# lamp-a-1.net
KiCad netlist of a schematic drawn in EAGLE
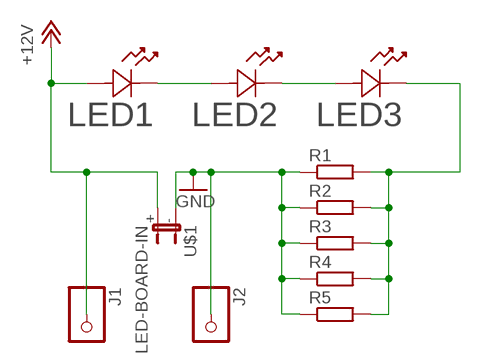
[diagram p0: schematic, sheet 1]

(export (version "E")
  (design (tool "Eeschema 10.0.6"))
  (components
    (comp (ref "J1")
      (value "LARGE-SOLDERPAD")
      (footprint "eagle-import:LARGE-SOLDERPAD")
      (libsource (lib "eagle-import") (part "LARGE-SOLDERPAD"))
    )
    (comp (ref "J2")
      (value "LARGE-SOLDERPAD")
      (footprint "eagle-import:LARGE-SOLDERPAD")
      (libsource (lib "eagle-import") (part "LARGE-SOLDERPAD"))
    )
    (comp (ref "LED1")
      (value "LED-2835LED_J2835_CRW-M")
      (footprint "eagle-import:LED_J2835_CRW-M")
      (fields
        (field (name "MANUFACTURER_PART_NUMBER") "JB2835AWT-W-U30GA0000-N0000001")
        (field (name "COPYRIGHT") "Copyright (C) 2024 Ultra Librarian. All rights reserved.")
      )
      (libsource (lib "eagle-import") (part "LED-2835LED_J2835_CRW-M"))
    )
    (comp (ref "LED2")
      (value "LED-2835LED_J2835_CRW-M")
      (footprint "eagle-import:LED_J2835_CRW-M")
      (fields
        (field (name "MANUFACTURER_PART_NUMBER") "JB2835AWT-W-U30GA0000-N0000001")
        (field (name "COPYRIGHT") "Copyright (C) 2024 Ultra Librarian. All rights reserved.")
      )
      (libsource (lib "eagle-import") (part "LED-2835LED_J2835_CRW-M"))
    )
    (comp (ref "LED3")
      (value "LED-2835LED_J2835_CRW-M")
      (footprint "eagle-import:LED_J2835_CRW-M")
      (fields
        (field (name "MANUFACTURER_PART_NUMBER") "JB2835AWT-W-U30GA0000-N0000001")
        (field (name "COPYRIGHT") "Copyright (C) 2024 Ultra Librarian. All rights reserved.")
      )
      (libsource (lib "eagle-import") (part "LED-2835LED_J2835_CRW-M"))
    )
    (comp (ref "R1")
      (value "R-EU_R0805")
      (footprint "eagle-import:R0805")
      (libsource (lib "eagle-import") (part "R-EU_R0805"))
    )
    (comp (ref "R2")
      (value "R-EU_R0805")
      (footprint "eagle-import:R0805")
      (libsource (lib "eagle-import") (part "R-EU_R0805"))
    )
    (comp (ref "R3")
      (value "R-EU_R0805")
      (footprint "eagle-import:R0805")
      (libsource (lib "eagle-import") (part "R-EU_R0805"))
    )
    (comp (ref "R4")
      (value "R-EU_R0805")
      (footprint "eagle-import:R0805")
      (libsource (lib "eagle-import") (part "R-EU_R0805"))
    )
    (comp (ref "R5")
      (value "R-EU_R0805")
      (footprint "eagle-import:R0805")
      (libsource (lib "eagle-import") (part "R-EU_R0805"))
    )
    (comp (ref "U$1")
      (value "LED-BOARD-IN")
      (footprint "eagle-import:LED-BOARD-IN")
      (libsource (lib "eagle-import") (part "LED-BOARD-IN"))
    )
  )
  (nets
    (net (code "1") (name "+12V") (class "Default")
      (node (ref "J1") (pin "P$1") (pinfunction "1_P$1") (pintype "passive"))
      (node (ref "LED1") (pin "2") (pinfunction "2_2") (pintype "passive"))
      (node (ref "U$1") (pin "+") (pinfunction "2_+") (pintype "passive"))
    )
    (net (code "2") (name "GND") (class "Default")
      (node (ref "J2") (pin "P$1") (pinfunction "1_P$1") (pintype "passive"))
      (node (ref "R1") (pin "1") (pinfunction "1_1") (pintype "passive"))
      (node (ref "R2") (pin "1") (pinfunction "1_1") (pintype "passive"))
      (node (ref "R3") (pin "1") (pinfunction "1_1") (pintype "passive"))
      (node (ref "R4") (pin "1") (pinfunction "1_1") (pintype "passive"))
      (node (ref "R5") (pin "1") (pinfunction "1_1") (pintype "passive"))
      (node (ref "U$1") (pin "-") (pinfunction "1_-") (pintype "passive"))
    )
    (net (code "3") (name "Net-(LED1-Pad1)") (class "Default")
      (node (ref "LED1") (pin "1") (pinfunction "1_1") (pintype "passive"))
      (node (ref "LED2") (pin "2") (pinfunction "2_2") (pintype "passive"))
    )
    (net (code "4") (name "Net-(LED2-Pad1)") (class "Default")
      (node (ref "LED2") (pin "1") (pinfunction "1_1") (pintype "passive"))
      (node (ref "LED3") (pin "2") (pinfunction "2_2") (pintype "passive"))
    )
    (net (code "5") (name "Net-(LED3-Pad1)") (class "Default")
      (node (ref "LED3") (pin "1") (pinfunction "1_1") (pintype "passive"))
      (node (ref "R1") (pin "2") (pinfunction "2_2") (pintype "passive"))
      (node (ref "R2") (pin "2") (pinfunction "2_2") (pintype "passive"))
      (node (ref "R3") (pin "2") (pinfunction "2_2") (pintype "passive"))
      (node (ref "R4") (pin "2") (pinfunction "2_2") (pintype "passive"))
      (node (ref "R5") (pin "2") (pinfunction "2_2") (pintype "passive"))
    )
  )
)
